# Sensor_Ada.net
KiCad netlist of a schematic drawn in EAGLE
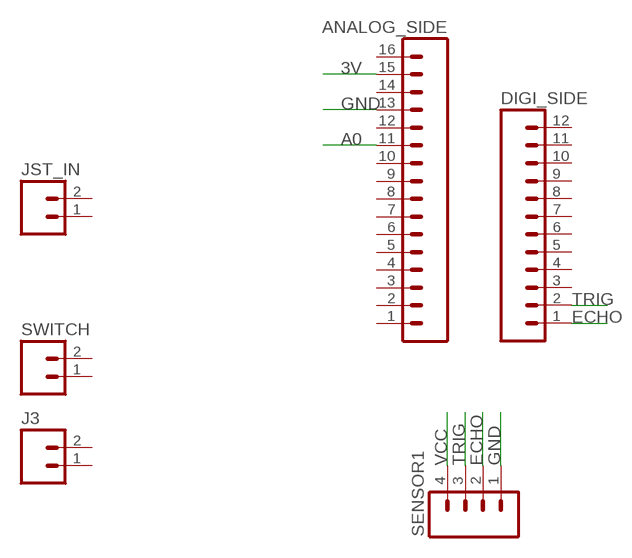
[diagram p0: schematic, sheet 1]

(export (version "E")
  (design (tool "Eeschema 10.0.6"))
  (components
    (comp (ref "ANALOG_SIDE")
      (value "M16LOCK")
      (footprint "eagle-import:1X16_LOCK")
      (libsource (lib "eagle-import") (part "M16LOCK"))
    )
    (comp (ref "DIGI_SIDE")
      (value "M12LOCK")
      (footprint "eagle-import:1X12_LOCK")
      (libsource (lib "eagle-import") (part "M12LOCK"))
    )
    (comp (ref "J3")
      (value "M02LOCK")
      (footprint "eagle-import:1X02_LOCK")
      (libsource (lib "eagle-import") (part "M02LOCK"))
    )
    (comp (ref "JST_IN")
      (value "M02JST-PTH-VERT")
      (footprint "eagle-import:JST-2-PTH-VERT")
      (libsource (lib "eagle-import") (part "M02JST-PTH-VERT"))
    )
    (comp (ref "SENSOR1")
      (value "M04LOCK")
      (footprint "eagle-import:1X04_LOCK")
      (libsource (lib "eagle-import") (part "M04LOCK"))
    )
    (comp (ref "SWITCH")
      (value "M02LOCK")
      (footprint "eagle-import:1X02_LOCK")
      (libsource (lib "eagle-import") (part "M02LOCK"))
    )
  )
  (nets
    (net (code "1") (name "/3V") (class "Default")
      (node (ref "ANALOG_SIDE") (pin "15") (pinfunction "15_15") (pintype "passive"))
    )
    (net (code "2") (name "/A0") (class "Default")
      (node (ref "ANALOG_SIDE") (pin "11") (pinfunction "11_11") (pintype "passive"))
    )
    (net (code "3") (name "/ECHO") (class "Default")
      (node (ref "DIGI_SIDE") (pin "1") (pinfunction "1_1") (pintype "passive"))
      (node (ref "SENSOR1") (pin "2") (pinfunction "2_2") (pintype "passive"))
    )
    (net (code "4") (name "/GND") (class "Default")
      (node (ref "ANALOG_SIDE") (pin "13") (pinfunction "13_13") (pintype "passive"))
      (node (ref "SENSOR1") (pin "1") (pinfunction "1_1") (pintype "passive"))
    )
    (net (code "5") (name "/TRIG") (class "Default")
      (node (ref "DIGI_SIDE") (pin "2") (pinfunction "2_2") (pintype "passive"))
      (node (ref "SENSOR1") (pin "3") (pinfunction "3_3") (pintype "passive"))
    )
    (net (code "6") (name "/VCC") (class "Default")
      (node (ref "SENSOR1") (pin "4") (pinfunction "4_4") (pintype "passive"))
    )
    (net (code "7") (name "unconnected-(ANALOG_SIDE-Pad1)") (class "Default")
      (node (ref "ANALOG_SIDE") (pin "1") (pinfunction "1_1") (pintype "passive"))
    )
    (net (code "8") (name "unconnected-(ANALOG_SIDE-Pad2)") (class "Default")
      (node (ref "ANALOG_SIDE") (pin "2") (pinfunction "2_2") (pintype "passive"))
    )
    (net (code "9") (name "unconnected-(ANALOG_SIDE-Pad3)") (class "Default")
      (node (ref "ANALOG_SIDE") (pin "3") (pinfunction "3_3") (pintype "passive"))
    )
    (net (code "10") (name "unconnected-(ANALOG_SIDE-Pad4)") (class "Default")
      (node (ref "ANALOG_SIDE") (pin "4") (pinfunction "4_4") (pintype "passive"))
    )
    (net (code "11") (name "unconnected-(ANALOG_SIDE-Pad5)") (class "Default")
      (node (ref "ANALOG_SIDE") (pin "5") (pinfunction "5_5") (pintype "passive"))
    )
    (net (code "12") (name "unconnected-(ANALOG_SIDE-Pad6)") (class "Default")
      (node (ref "ANALOG_SIDE") (pin "6") (pinfunction "6_6") (pintype "passive"))
    )
    (net (code "13") (name "unconnected-(ANALOG_SIDE-Pad7)") (class "Default")
      (node (ref "ANALOG_SIDE") (pin "7") (pinfunction "7_7") (pintype "passive"))
    )
    (net (code "14") (name "unconnected-(ANALOG_SIDE-Pad8)") (class "Default")
      (node (ref "ANALOG_SIDE") (pin "8") (pinfunction "8_8") (pintype "passive"))
    )
    (net (code "15") (name "unconnected-(ANALOG_SIDE-Pad9)") (class "Default")
      (node (ref "ANALOG_SIDE") (pin "9") (pinfunction "9_9") (pintype "passive"))
    )
    (net (code "16") (name "unconnected-(ANALOG_SIDE-Pad10)") (class "Default")
      (node (ref "ANALOG_SIDE") (pin "10") (pinfunction "10_10") (pintype "passive"))
    )
    (net (code "17") (name "unconnected-(ANALOG_SIDE-Pad12)") (class "Default")
      (node (ref "ANALOG_SIDE") (pin "12") (pinfunction "12_12") (pintype "passive"))
    )
    (net (code "18") (name "unconnected-(ANALOG_SIDE-Pad14)") (class "Default")
      (node (ref "ANALOG_SIDE") (pin "14") (pinfunction "14_14") (pintype "passive"))
    )
    (net (code "19") (name "unconnected-(ANALOG_SIDE-Pad16)") (class "Default")
      (node (ref "ANALOG_SIDE") (pin "16") (pinfunction "16_16") (pintype "passive"))
    )
    (net (code "20") (name "unconnected-(DIGI_SIDE-Pad3)") (class "Default")
      (node (ref "DIGI_SIDE") (pin "3") (pinfunction "3_3") (pintype "passive"))
    )
    (net (code "21") (name "unconnected-(DIGI_SIDE-Pad4)") (class "Default")
      (node (ref "DIGI_SIDE") (pin "4") (pinfunction "4_4") (pintype "passive"))
    )
    (net (code "22") (name "unconnected-(DIGI_SIDE-Pad5)") (class "Default")
      (node (ref "DIGI_SIDE") (pin "5") (pinfunction "5_5") (pintype "passive"))
    )
    (net (code "23") (name "unconnected-(DIGI_SIDE-Pad6)") (class "Default")
      (node (ref "DIGI_SIDE") (pin "6") (pinfunction "6_6") (pintype "passive"))
    )
    (net (code "24") (name "unconnected-(DIGI_SIDE-Pad7)") (class "Default")
      (node (ref "DIGI_SIDE") (pin "7") (pinfunction "7_7") (pintype "passive"))
    )
    (net (code "25") (name "unconnected-(DIGI_SIDE-Pad8)") (class "Default")
      (node (ref "DIGI_SIDE") (pin "8") (pinfunction "8_8") (pintype "passive"))
    )
    (net (code "26") (name "unconnected-(DIGI_SIDE-Pad9)") (class "Default")
      (node (ref "DIGI_SIDE") (pin "9") (pinfunction "9_9") (pintype "passive"))
    )
    (net (code "27") (name "unconnected-(DIGI_SIDE-Pad10)") (class "Default")
      (node (ref "DIGI_SIDE") (pin "10") (pinfunction "10_10") (pintype "passive"))
    )
    (net (code "28") (name "unconnected-(DIGI_SIDE-Pad11)") (class "Default")
      (node (ref "DIGI_SIDE") (pin "11") (pinfunction "11_11") (pintype "passive"))
    )
    (net (code "29") (name "unconnected-(DIGI_SIDE-Pad12)") (class "Default")
      (node (ref "DIGI_SIDE") (pin "12") (pinfunction "12_12") (pintype "passive"))
    )
    (net (code "30") (name "unconnected-(J3-Pad1)") (class "Default")
      (node (ref "J3") (pin "1") (pinfunction "1_1") (pintype "passive"))
    )
    (net (code "31") (name "unconnected-(J3-Pad2)") (class "Default")
      (node (ref "J3") (pin "2") (pinfunction "2_2") (pintype "passive"))
    )
    (net (code "32") (name "unconnected-(JST_IN-Pad1)") (class "Default")
      (node (ref "JST_IN") (pin "1") (pinfunction "1_1") (pintype "passive"))
    )
    (net (code "33") (name "unconnected-(JST_IN-Pad2)") (class "Default")
      (node (ref "JST_IN") (pin "2") (pinfunction "2_2") (pintype "passive"))
    )
    (net (code "34") (name "unconnected-(SWITCH-Pad1)") (class "Default")
      (node (ref "SWITCH") (pin "1") (pinfunction "1_1") (pintype "passive"))
    )
    (net (code "35") (name "unconnected-(SWITCH-Pad2)") (class "Default")
      (node (ref "SWITCH") (pin "2") (pinfunction "2_2") (pintype "passive"))
    )
  )
)
